# 3_DISPLAY.net
KiCad netlist of a schematic drawn in Altium Designer
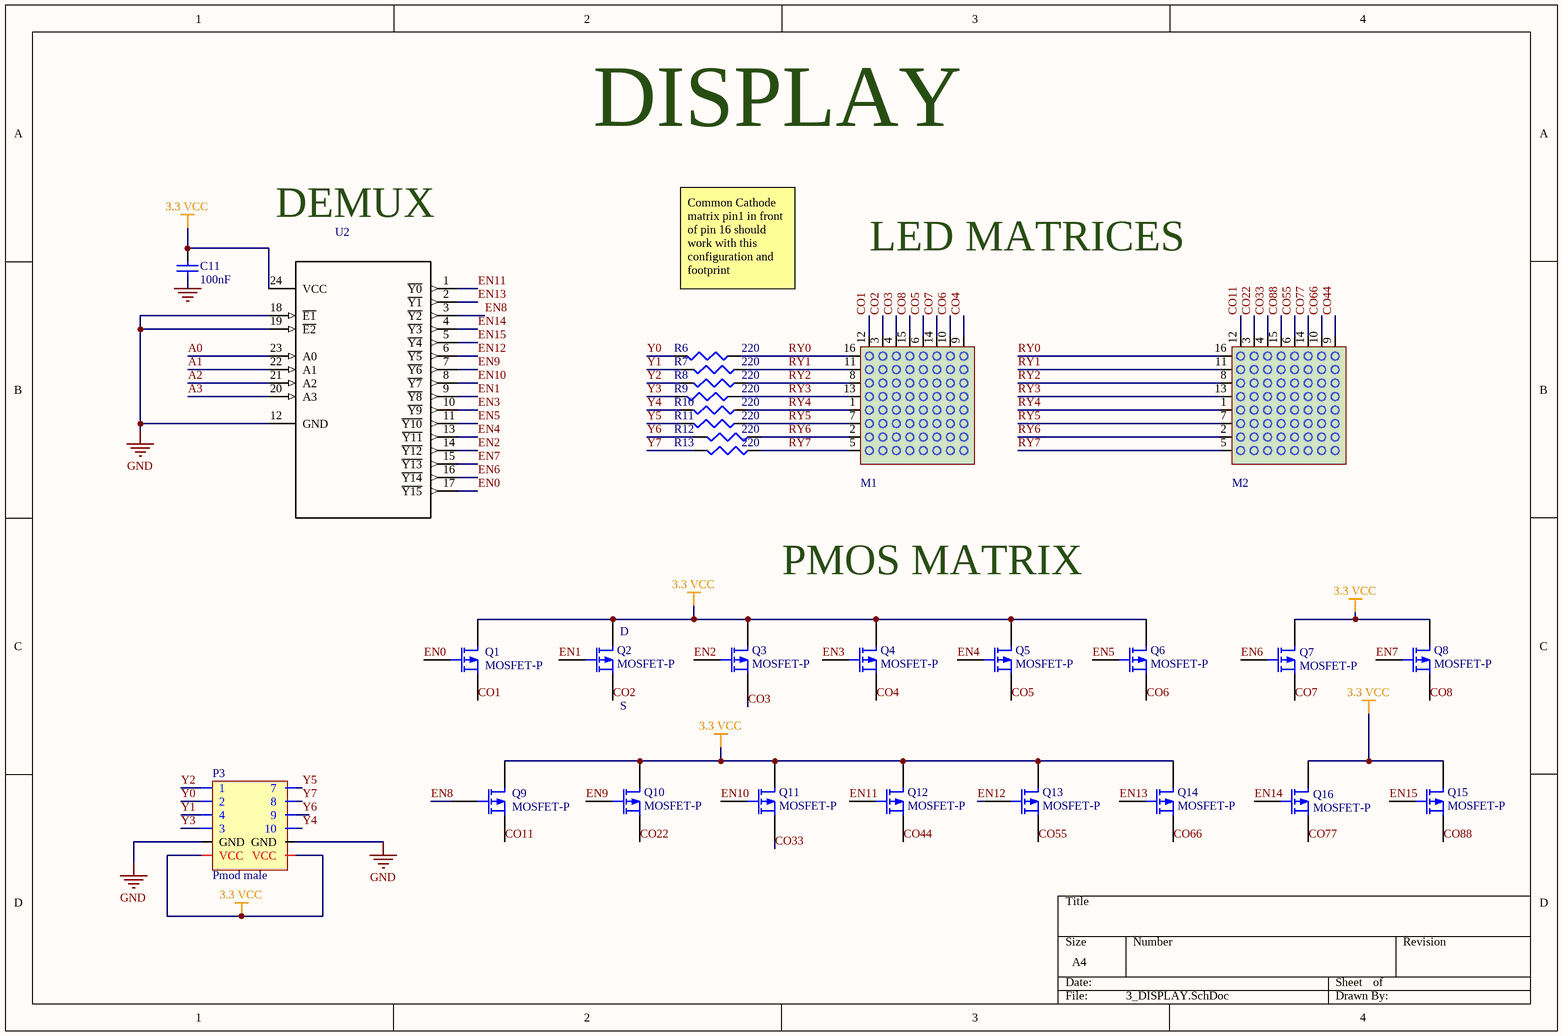
[diagram p0: 3_DISPLAY.SchDoc]

(export (version "E")
  (design (tool "Eeschema 10.0.6"))
  (components
    (comp (ref "C11")
      (value "100nF")
      (footprint "1608[0603]")
      (description "Capacitor (Semiconductor SIM Model)")
      (fields (field (name "Comment") "Cap Semi") (field (name "PUBLISHER") "Altium Limited"))
      (libsource (lib "Miscellaneous Devices") (part "Cap Semi"))
    )
    (comp (ref "M1")
      (value "matrix8X8")
      (footprint "Matrix Led")
      (libsource (lib "Schlib1") (part "matrix8X8"))
    )
    (comp (ref "M2")
      (value "matrix8X8")
      (footprint "Matrix Led")
      (libsource (lib "Schlib1") (part "matrix8X8"))
    )
    (comp (ref "P3")
      (value "Pmod male")
      (footprint "901220766")
      (description "p mod male 6 position 2 rows")
      (libsource (lib "Schlib1") (part "Pmod male"))
    )
    (comp (ref "Q1")
      (value "MOSFET-P")
      (footprint "BSS84PWH6327XTSA1")
      (description "P-Channel MOSFET")
      (fields (field (name "PUBLISHER") "Altium Limited"))
      (libsource (lib "Miscellaneous Devices") (part "MOSFET-P"))
    )
    (comp (ref "Q2")
      (value "MOSFET-P")
      (footprint "BSS84PWH6327XTSA1")
      (description "P-Channel MOSFET")
      (fields (field (name "PUBLISHER") "Altium Limited"))
      (libsource (lib "Miscellaneous Devices") (part "MOSFET-P"))
    )
    (comp (ref "Q3")
      (value "MOSFET-P")
      (footprint "BSS84PWH6327XTSA1")
      (description "P-Channel MOSFET")
      (fields (field (name "PUBLISHER") "Altium Limited"))
      (libsource (lib "Miscellaneous Devices") (part "MOSFET-P"))
    )
    (comp (ref "Q4")
      (value "MOSFET-P")
      (footprint "BSS84PWH6327XTSA1")
      (description "P-Channel MOSFET")
      (fields (field (name "PUBLISHER") "Altium Limited"))
      (libsource (lib "Miscellaneous Devices") (part "MOSFET-P"))
    )
    (comp (ref "Q5")
      (value "MOSFET-P")
      (footprint "BSS84PWH6327XTSA1")
      (description "P-Channel MOSFET")
      (fields (field (name "PUBLISHER") "Altium Limited"))
      (libsource (lib "Miscellaneous Devices") (part "MOSFET-P"))
    )
    (comp (ref "Q6")
      (value "MOSFET-P")
      (footprint "BSS84PWH6327XTSA1")
      (description "P-Channel MOSFET")
      (fields (field (name "PUBLISHER") "Altium Limited"))
      (libsource (lib "Miscellaneous Devices") (part "MOSFET-P"))
    )
    (comp (ref "Q7")
      (value "MOSFET-P")
      (footprint "BSS84PWH6327XTSA1")
      (description "P-Channel MOSFET")
      (fields (field (name "PUBLISHER") "Altium Limited"))
      (libsource (lib "Miscellaneous Devices") (part "MOSFET-P"))
    )
    (comp (ref "Q8")
      (value "MOSFET-P")
      (footprint "BSS84PWH6327XTSA1")
      (description "P-Channel MOSFET")
      (fields (field (name "PUBLISHER") "Altium Limited"))
      (libsource (lib "Miscellaneous Devices") (part "MOSFET-P"))
    )
    (comp (ref "Q9")
      (value "MOSFET-P")
      (footprint "BSS84PWH6327XTSA1")
      (description "P-Channel MOSFET")
      (fields (field (name "PUBLISHER") "Altium Limited"))
      (libsource (lib "Miscellaneous Devices") (part "MOSFET-P"))
    )
    (comp (ref "Q10")
      (value "MOSFET-P")
      (footprint "BSS84PWH6327XTSA1")
      (description "P-Channel MOSFET")
      (fields (field (name "PUBLISHER") "Altium Limited"))
      (libsource (lib "Miscellaneous Devices") (part "MOSFET-P"))
    )
    (comp (ref "Q11")
      (value "MOSFET-P")
      (footprint "BSS84PWH6327XTSA1")
      (description "P-Channel MOSFET")
      (fields (field (name "PUBLISHER") "Altium Limited"))
      (libsource (lib "Miscellaneous Devices") (part "MOSFET-P"))
    )
    (comp (ref "Q12")
      (value "MOSFET-P")
      (footprint "BSS84PWH6327XTSA1")
      (description "P-Channel MOSFET")
      (fields (field (name "PUBLISHER") "Altium Limited"))
      (libsource (lib "Miscellaneous Devices") (part "MOSFET-P"))
    )
    (comp (ref "Q13")
      (value "MOSFET-P")
      (footprint "BSS84PWH6327XTSA1")
      (description "P-Channel MOSFET")
      (fields (field (name "PUBLISHER") "Altium Limited"))
      (libsource (lib "Miscellaneous Devices") (part "MOSFET-P"))
    )
    (comp (ref "Q14")
      (value "MOSFET-P")
      (footprint "BSS84PWH6327XTSA1")
      (description "P-Channel MOSFET")
      (fields (field (name "PUBLISHER") "Altium Limited"))
      (libsource (lib "Miscellaneous Devices") (part "MOSFET-P"))
    )
    (comp (ref "Q15")
      (value "MOSFET-P")
      (footprint "BSS84PWH6327XTSA1")
      (description "P-Channel MOSFET")
      (fields (field (name "PUBLISHER") "Altium Limited"))
      (libsource (lib "Miscellaneous Devices") (part "MOSFET-P"))
    )
    (comp (ref "Q16")
      (value "MOSFET-P")
      (footprint "BSS84PWH6327XTSA1")
      (description "P-Channel MOSFET")
      (fields (field (name "PUBLISHER") "Altium Limited"))
      (libsource (lib "Miscellaneous Devices") (part "MOSFET-P"))
    )
    (comp (ref "R6")
      (value "220")
      (footprint "Resistor 0805")
      (description "Resistor")
      (fields (field (name "Comment") "270R") (field (name "PUBLISHER") "Altium Limited"))
      (libsource (lib "Miscellaneous Devices") (part "Res3"))
    )
    (comp (ref "R7")
      (value "220")
      (footprint "Resistor 0805")
      (description "Resistor")
      (fields (field (name "Comment") "270R") (field (name "PUBLISHER") "Altium Limited"))
      (libsource (lib "Miscellaneous Devices") (part "Res3"))
    )
    (comp (ref "R8")
      (value "220")
      (footprint "Resistor 0805")
      (description "Resistor")
      (fields (field (name "Comment") "270R") (field (name "PUBLISHER") "Altium Limited"))
      (libsource (lib "Miscellaneous Devices") (part "Res3"))
    )
    (comp (ref "R9")
      (value "220")
      (footprint "Resistor 0805")
      (description "Resistor")
      (fields (field (name "Comment") "270R") (field (name "PUBLISHER") "Altium Limited"))
      (libsource (lib "Miscellaneous Devices") (part "Res3"))
    )
    (comp (ref "R10")
      (value "220")
      (footprint "Resistor 0805")
      (description "Resistor")
      (fields (field (name "Comment") "270R") (field (name "PUBLISHER") "Altium Limited"))
      (libsource (lib "Miscellaneous Devices") (part "Res3"))
    )
    (comp (ref "R11")
      (value "220")
      (footprint "Resistor 0805")
      (description "Resistor")
      (fields (field (name "Comment") "270R") (field (name "PUBLISHER") "Altium Limited"))
      (libsource (lib "Miscellaneous Devices") (part "Res3"))
    )
    (comp (ref "R12")
      (value "220")
      (footprint "Resistor 0805")
      (description "Resistor")
      (fields (field (name "Comment") "270R") (field (name "PUBLISHER") "Altium Limited"))
      (libsource (lib "Miscellaneous Devices") (part "Res3"))
    )
    (comp (ref "R13")
      (value "220")
      (footprint "Resistor 0805")
      (description "Resistor")
      (fields (field (name "Comment") "270R") (field (name "PUBLISHER") "Altium Limited"))
      (libsource (lib "Miscellaneous Devices") (part "Res3"))
    )
    (comp (ref "U2")
      (value "CD74HC154M")
      (footprint "*SOIC127P1030X265-24N")
      (description "Decoder/Demultiplexer 1 x 4:16 24-SOIC")
      (fields (field (name "MF") "Texas Instruments"))
      (libsource (lib "Schlib1") (part "CD74HC154M"))
    )
  )
  (nets
    (net (code "1") (name "/A0") (class "Default")
      (node (ref "U2") (pin "23") (pinfunction "A0_23") (pintype "input"))
    )
    (net (code "2") (name "/A1") (class "Default")
      (node (ref "U2") (pin "22") (pinfunction "A1_22") (pintype "input"))
    )
    (net (code "3") (name "/A2") (class "Default")
      (node (ref "U2") (pin "21") (pinfunction "A2_21") (pintype "input"))
    )
    (net (code "4") (name "/A3") (class "Default")
      (node (ref "U2") (pin "20") (pinfunction "A3_20") (pintype "input"))
    )
    (net (code "5") (name "/CO1") (class "Default")
      (node (ref "M1") (pin "12") (pinfunction "12_12") (pintype "output"))
      (node (ref "Q1") (pin "2") (pinfunction "S_2") (pintype "passive"))
    )
    (net (code "6") (name "/CO2") (class "Default")
      (node (ref "M1") (pin "3") (pinfunction "7_3") (pintype "output"))
      (node (ref "Q2") (pin "2") (pinfunction "S_2") (pintype "passive"))
    )
    (net (code "7") (name "/CO3") (class "Default")
      (node (ref "M1") (pin "4") (pinfunction "8_4") (pintype "output"))
      (node (ref "Q3") (pin "2") (pinfunction "S_2") (pintype "passive"))
    )
    (net (code "8") (name "/CO4") (class "Default")
      (node (ref "M1") (pin "9") (pinfunction "9_9") (pintype "output"))
      (node (ref "Q4") (pin "2") (pinfunction "S_2") (pintype "passive"))
    )
    (net (code "9") (name "/CO5") (class "Default")
      (node (ref "M1") (pin "6") (pinfunction "10_6") (pintype "output"))
      (node (ref "Q5") (pin "2") (pinfunction "S_2") (pintype "passive"))
    )
    (net (code "10") (name "/CO6") (class "Default")
      (node (ref "M1") (pin "10") (pinfunction "10_10") (pintype "output"))
      (node (ref "Q6") (pin "2") (pinfunction "S_2") (pintype "passive"))
    )
    (net (code "11") (name "/CO7") (class "Default")
      (node (ref "M1") (pin "14") (pinfunction "14_14") (pintype "output"))
      (node (ref "Q7") (pin "2") (pinfunction "S_2") (pintype "passive"))
    )
    (net (code "12") (name "/CO8") (class "Default")
      (node (ref "M1") (pin "15") (pinfunction "15_15") (pintype "output"))
      (node (ref "Q8") (pin "2") (pinfunction "S_2") (pintype "passive"))
    )
    (net (code "13") (name "/CO11") (class "Default")
      (node (ref "M2") (pin "12") (pinfunction "12_12") (pintype "output"))
      (node (ref "Q9") (pin "2") (pinfunction "S_2") (pintype "passive"))
    )
    (net (code "14") (name "/CO22") (class "Default")
      (node (ref "M2") (pin "3") (pinfunction "7_3") (pintype "output"))
      (node (ref "Q10") (pin "2") (pinfunction "S_2") (pintype "passive"))
    )
    (net (code "15") (name "/CO33") (class "Default")
      (node (ref "M2") (pin "4") (pinfunction "8_4") (pintype "output"))
      (node (ref "Q11") (pin "2") (pinfunction "S_2") (pintype "passive"))
    )
    (net (code "16") (name "/CO44") (class "Default")
      (node (ref "M2") (pin "9") (pinfunction "9_9") (pintype "output"))
      (node (ref "Q12") (pin "2") (pinfunction "S_2") (pintype "passive"))
    )
    (net (code "17") (name "/CO55") (class "Default")
      (node (ref "M2") (pin "6") (pinfunction "10_6") (pintype "output"))
      (node (ref "Q13") (pin "2") (pinfunction "S_2") (pintype "passive"))
    )
    (net (code "18") (name "/CO66") (class "Default")
      (node (ref "M2") (pin "10") (pinfunction "10_10") (pintype "output"))
      (node (ref "Q14") (pin "2") (pinfunction "S_2") (pintype "passive"))
    )
    (net (code "19") (name "/CO77") (class "Default")
      (node (ref "M2") (pin "14") (pinfunction "14_14") (pintype "output"))
      (node (ref "Q16") (pin "2") (pinfunction "S_2") (pintype "passive"))
    )
    (net (code "20") (name "/CO88") (class "Default")
      (node (ref "M2") (pin "15") (pinfunction "15_15") (pintype "output"))
      (node (ref "Q15") (pin "2") (pinfunction "S_2") (pintype "passive"))
    )
    (net (code "21") (name "/EN0") (class "Default")
      (node (ref "Q1") (pin "1") (pinfunction "G_1") (pintype "passive"))
      (node (ref "U2") (pin "17") (pinfunction "~{Y15}_17") (pintype "output"))
    )
    (net (code "22") (name "/EN1") (class "Default")
      (node (ref "Q2") (pin "1") (pinfunction "G_1") (pintype "passive"))
      (node (ref "U2") (pin "9") (pinfunction "~{Y8}_9") (pintype "output"))
    )
    (net (code "23") (name "/EN2") (class "Default")
      (node (ref "Q3") (pin "1") (pinfunction "G_1") (pintype "passive"))
      (node (ref "U2") (pin "14") (pinfunction "~{Y12}_14") (pintype "output"))
    )
    (net (code "24") (name "/EN3") (class "Default")
      (node (ref "Q4") (pin "1") (pinfunction "G_1") (pintype "passive"))
      (node (ref "U2") (pin "10") (pinfunction "~{Y9}_10") (pintype "output"))
    )
    (net (code "25") (name "/EN4") (class "Default")
      (node (ref "Q5") (pin "1") (pinfunction "G_1") (pintype "passive"))
      (node (ref "U2") (pin "13") (pinfunction "~{Y11}_13") (pintype "output"))
    )
    (net (code "26") (name "/EN5") (class "Default")
      (node (ref "Q6") (pin "1") (pinfunction "G_1") (pintype "passive"))
      (node (ref "U2") (pin "11") (pinfunction "~{Y10}_11") (pintype "output"))
    )
    (net (code "27") (name "/EN6") (class "Default")
      (node (ref "Q7") (pin "1") (pinfunction "G_1") (pintype "passive"))
      (node (ref "U2") (pin "16") (pinfunction "~{Y14}_16") (pintype "output"))
    )
    (net (code "28") (name "/EN7") (class "Default")
      (node (ref "Q8") (pin "1") (pinfunction "G_1") (pintype "passive"))
      (node (ref "U2") (pin "15") (pinfunction "~{Y13}_15") (pintype "output"))
    )
    (net (code "29") (name "/EN8") (class "Default")
      (node (ref "Q9") (pin "1") (pinfunction "G_1") (pintype "passive"))
      (node (ref "U2") (pin "3") (pinfunction "~{Y2}_3") (pintype "output"))
    )
    (net (code "30") (name "/EN9") (class "Default")
      (node (ref "Q10") (pin "1") (pinfunction "G_1") (pintype "passive"))
      (node (ref "U2") (pin "7") (pinfunction "~{Y6}_7") (pintype "output"))
    )
    (net (code "31") (name "/EN10") (class "Default")
      (node (ref "Q11") (pin "1") (pinfunction "G_1") (pintype "passive"))
      (node (ref "U2") (pin "8") (pinfunction "~{Y7}_8") (pintype "output"))
    )
    (net (code "32") (name "/EN11") (class "Default")
      (node (ref "Q12") (pin "1") (pinfunction "G_1") (pintype "passive"))
      (node (ref "U2") (pin "1") (pinfunction "~{Y0}_1") (pintype "output"))
    )
    (net (code "33") (name "/EN12") (class "Default")
      (node (ref "Q13") (pin "1") (pinfunction "G_1") (pintype "passive"))
      (node (ref "U2") (pin "6") (pinfunction "~{Y5}_6") (pintype "output"))
    )
    (net (code "34") (name "/EN13") (class "Default")
      (node (ref "Q14") (pin "1") (pinfunction "G_1") (pintype "passive"))
      (node (ref "U2") (pin "2") (pinfunction "~{Y1}_2") (pintype "output"))
    )
    (net (code "35") (name "/EN14") (class "Default")
      (node (ref "Q16") (pin "1") (pinfunction "G_1") (pintype "passive"))
      (node (ref "U2") (pin "4") (pinfunction "~{Y3}_4") (pintype "output"))
    )
    (net (code "36") (name "/EN15") (class "Default")
      (node (ref "Q15") (pin "1") (pinfunction "G_1") (pintype "passive"))
      (node (ref "U2") (pin "5") (pinfunction "~{Y4}_5") (pintype "output"))
    )
    (net (code "37") (name "/RY0") (class "Default")
      (node (ref "M1") (pin "16") (pinfunction "16_16") (pintype "input"))
      (node (ref "M2") (pin "16") (pinfunction "16_16") (pintype "input"))
      (node (ref "R6") (pin "1") (pinfunction "1_1") (pintype "passive"))
    )
    (net (code "38") (name "/RY1") (class "Default")
      (node (ref "M1") (pin "11") (pinfunction "11_11") (pintype "input"))
      (node (ref "M2") (pin "11") (pinfunction "11_11") (pintype "input"))
      (node (ref "R7") (pin "1") (pinfunction "1_1") (pintype "passive"))
    )
    (net (code "39") (name "/RY2") (class "Default")
      (node (ref "M1") (pin "8") (pinfunction "8_8") (pintype "input"))
      (node (ref "M2") (pin "8") (pinfunction "8_8") (pintype "input"))
      (node (ref "R8") (pin "1") (pinfunction "1_1") (pintype "passive"))
    )
    (net (code "40") (name "/RY3") (class "Default")
      (node (ref "M1") (pin "13") (pinfunction "13_13") (pintype "input"))
      (node (ref "M2") (pin "13") (pinfunction "13_13") (pintype "input"))
      (node (ref "R9") (pin "1") (pinfunction "1_1") (pintype "passive"))
    )
    (net (code "41") (name "/RY4") (class "Default")
      (node (ref "M1") (pin "1") (pinfunction "5_1") (pintype "input"))
      (node (ref "M2") (pin "1") (pinfunction "5_1") (pintype "input"))
      (node (ref "R10") (pin "1") (pinfunction "1_1") (pintype "passive"))
    )
    (net (code "42") (name "/RY5") (class "Default")
      (node (ref "M1") (pin "7") (pinfunction "7_7") (pintype "input"))
      (node (ref "M2") (pin "7") (pinfunction "7_7") (pintype "input"))
      (node (ref "R11") (pin "1") (pinfunction "1_1") (pintype "passive"))
    )
    (net (code "43") (name "/RY6") (class "Default")
      (node (ref "M1") (pin "2") (pinfunction "6_2") (pintype "input"))
      (node (ref "M2") (pin "2") (pinfunction "6_2") (pintype "input"))
      (node (ref "R12") (pin "1") (pinfunction "1_1") (pintype "passive"))
    )
    (net (code "44") (name "/RY7") (class "Default")
      (node (ref "M1") (pin "5") (pinfunction "9_5") (pintype "input"))
      (node (ref "M2") (pin "5") (pinfunction "9_5") (pintype "input"))
      (node (ref "R13") (pin "1") (pinfunction "1_1") (pintype "passive"))
    )
    (net (code "45") (name "/Y0") (class "Default")
      (node (ref "P3") (pin "2") (pinfunction "2_2") (pintype "passive"))
      (node (ref "R6") (pin "2") (pinfunction "2_2") (pintype "passive"))
    )
    (net (code "46") (name "/Y1") (class "Default")
      (node (ref "P3") (pin "4") (pinfunction "4_4") (pintype "passive"))
      (node (ref "R7") (pin "2") (pinfunction "2_2") (pintype "passive"))
    )
    (net (code "47") (name "/Y2") (class "Default")
      (node (ref "P3") (pin "1") (pinfunction "1_1") (pintype "passive"))
      (node (ref "R8") (pin "2") (pinfunction "2_2") (pintype "passive"))
    )
    (net (code "48") (name "/Y3") (class "Default")
      (node (ref "P3") (pin "3") (pinfunction "3_3") (pintype "passive"))
      (node (ref "R9") (pin "2") (pinfunction "2_2") (pintype "passive"))
    )
    (net (code "49") (name "/Y4") (class "Default")
      (node (ref "P3") (pin "10") (pinfunction "10_10") (pintype "passive"))
      (node (ref "R10") (pin "2") (pinfunction "2_2") (pintype "passive"))
    )
    (net (code "50") (name "/Y5") (class "Default")
      (node (ref "P3") (pin "7") (pinfunction "7_7") (pintype "passive"))
      (node (ref "R11") (pin "2") (pinfunction "2_2") (pintype "passive"))
    )
    (net (code "51") (name "/Y6") (class "Default")
      (node (ref "P3") (pin "9") (pinfunction "9_9") (pintype "passive"))
      (node (ref "R12") (pin "2") (pinfunction "2_2") (pintype "passive"))
    )
    (net (code "52") (name "/Y7") (class "Default")
      (node (ref "P3") (pin "8") (pinfunction "8_8") (pintype "passive"))
      (node (ref "R13") (pin "2") (pinfunction "2_2") (pintype "passive"))
    )
    (net (code "53") (name "3.3 VCC") (class "Default")
      (node (ref "C11") (pin "1") (pinfunction "1_1") (pintype "passive"))
      (node (ref "P3") (pin "12") (pinfunction "VCC_12") (pintype "passive"))
      (node (ref "P3") (pin "6") (pinfunction "VCC_6") (pintype "passive"))
      (node (ref "Q1") (pin "3") (pinfunction "D_3") (pintype "passive"))
      (node (ref "Q10") (pin "3") (pinfunction "D_3") (pintype "passive"))
      (node (ref "Q11") (pin "3") (pinfunction "D_3") (pintype "passive"))
      (node (ref "Q12") (pin "3") (pinfunction "D_3") (pintype "passive"))
      (node (ref "Q13") (pin "3") (pinfunction "D_3") (pintype "passive"))
      (node (ref "Q14") (pin "3") (pinfunction "D_3") (pintype "passive"))
      (node (ref "Q15") (pin "3") (pinfunction "D_3") (pintype "passive"))
      (node (ref "Q16") (pin "3") (pinfunction "D_3") (pintype "passive"))
      (node (ref "Q2") (pin "3") (pinfunction "D_3") (pintype "passive"))
      (node (ref "Q3") (pin "3") (pinfunction "D_3") (pintype "passive"))
      (node (ref "Q4") (pin "3") (pinfunction "D_3") (pintype "passive"))
      (node (ref "Q5") (pin "3") (pinfunction "D_3") (pintype "passive"))
      (node (ref "Q6") (pin "3") (pinfunction "D_3") (pintype "passive"))
      (node (ref "Q7") (pin "3") (pinfunction "D_3") (pintype "passive"))
      (node (ref "Q8") (pin "3") (pinfunction "D_3") (pintype "passive"))
      (node (ref "Q9") (pin "3") (pinfunction "D_3") (pintype "passive"))
      (node (ref "U2") (pin "24") (pinfunction "VCC_24") (pintype "power_in"))
    )
    (net (code "54") (name "GND") (class "Default")
      (node (ref "C11") (pin "2") (pinfunction "2_2") (pintype "passive"))
      (node (ref "P3") (pin "11") (pinfunction "GND_11") (pintype "passive"))
      (node (ref "P3") (pin "5") (pinfunction "GND_5") (pintype "passive"))
      (node (ref "U2") (pin "12") (pinfunction "GND_12") (pintype "passive"))
      (node (ref "U2") (pin "18") (pinfunction "~{E1}_18") (pintype "input"))
      (node (ref "U2") (pin "19") (pinfunction "~{E2}_19") (pintype "input"))
    )
  )
)
